# Schematic.net
KiCad netlist of a schematic drawn in Altium Designer
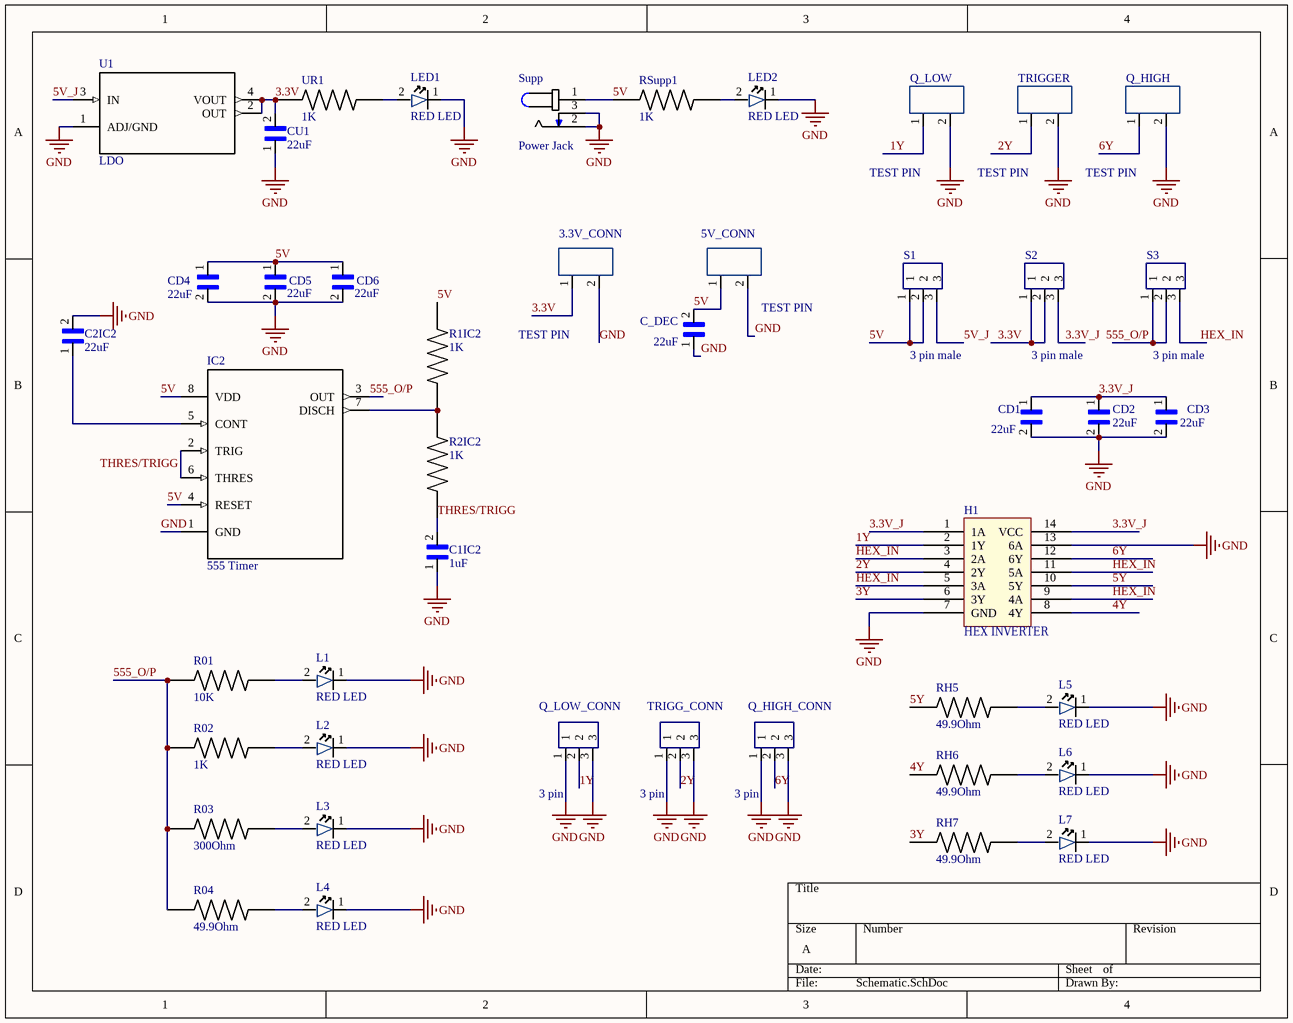
[diagram p0: Schematic.SchDoc]

(export (version "E")
  (design (tool "Eeschema 10.0.6"))
  (components
    (comp (ref "3.3V_CONN")
      (value "TEST PIN")
      (footprint "TEST_PINS")
      (libsource (lib "Components") (part "TEST PIN"))
    )
    (comp (ref "5V_CONN")
      (value "TEST PIN")
      (footprint "TEST_PINS")
      (libsource (lib "Components") (part "TEST PIN"))
    )
    (comp (ref "C1IC2")
      (value "1uF")
      (footprint "1206_PASSIVE")
      (description "CAP CER 1UF 16V X7R 1206")
      (fields (field (name "DIGIKEY PART") "‎399-8150-1-ND‎"))
      (libsource (lib "Components") (part "C1206C105M4RACTU‎"))
    )
    (comp (ref "C2IC2")
      (value "22uF")
      (footprint "1206_PASSIVE")
      (description "CAP CER 22UF 16V X5R 1206")
      (fields (field (name "DIGIKEY PART") "‎1276-2728-1-ND‎"))
      (libsource (lib "Components") (part "CL31A226MOCLNNC‎"))
    )
    (comp (ref "CD1")
      (value "22uF")
      (footprint "1206_PASSIVE")
      (description "CAP CER 22UF 16V X5R 1206")
      (fields (field (name "DIGIKEY PART") "‎1276-2728-1-ND‎"))
      (libsource (lib "Components") (part "CL31A226MOCLNNC‎"))
    )
    (comp (ref "CD2")
      (value "22uF")
      (footprint "1206_PASSIVE")
      (description "CAP CER 22UF 16V X5R 1206")
      (fields (field (name "DIGIKEY PART") "‎1276-2728-1-ND‎"))
      (libsource (lib "Components") (part "CL31A226MOCLNNC‎"))
    )
    (comp (ref "CD3")
      (value "22uF")
      (footprint "1206_PASSIVE")
      (description "CAP CER 22UF 16V X5R 1206")
      (fields (field (name "DIGIKEY PART") "‎1276-2728-1-ND‎"))
      (libsource (lib "Components") (part "CL31A226MOCLNNC‎"))
    )
    (comp (ref "CD4")
      (value "22uF")
      (footprint "1206_PASSIVE")
      (description "CAP CER 22UF 16V X5R 1206")
      (fields (field (name "DIGIKEY PART") "‎1276-2728-1-ND‎"))
      (libsource (lib "Components") (part "CL31A226MOCLNNC‎"))
    )
    (comp (ref "CD5")
      (value "22uF")
      (footprint "1206_PASSIVE")
      (description "CAP CER 22UF 16V X5R 1206")
      (fields (field (name "DIGIKEY PART") "‎1276-2728-1-ND‎"))
      (libsource (lib "Components") (part "CL31A226MOCLNNC‎"))
    )
    (comp (ref "CD6")
      (value "22uF")
      (footprint "1206_PASSIVE")
      (description "CAP CER 22UF 16V X5R 1206")
      (fields (field (name "DIGIKEY PART") "‎1276-2728-1-ND‎"))
      (libsource (lib "Components") (part "CL31A226MOCLNNC‎"))
    )
    (comp (ref "CU1")
      (value "22uF")
      (footprint "1206_PASSIVE")
      (description "CAP CER 22UF 16V X5R 1206")
      (fields (field (name "DIGIKEY PART") "‎1276-2728-1-ND‎"))
      (libsource (lib "Components") (part "CL31A226MOCLNNC‎"))
    )
    (comp (ref "C_DEC")
      (value "22uF")
      (footprint "1206_PASSIVE")
      (description "CAP CER 22UF 16V X5R 1206")
      (fields (field (name "DIGIKEY PART") "‎1276-2728-1-ND‎"))
      (libsource (lib "Components") (part "CL31A226MOCLNNC‎"))
    )
    (comp (ref "H1")
      (value "‎HEX INVERTER")
      (footprint "HEX")
      (description "IC INVERTER SCHMITT 6CH 14SOP")
      (fields (field (name "DIGIKEY PART") "‎296-28498-1-ND‎"))
      (libsource (lib "Components") (part "‎SN74ALVC14NSR‎"))
    )
    (comp (ref "IC2")
      (value "555 Timer")
      (footprint "555")
      (description "IC OSC SGL TIMER 2.1MHZ 8-SOIC")
      (fields (field (name "DIGIKEY PART") "‎296-1336-1-ND‎"))
      (libsource (lib "Components") (part "‎TLC555CDR‎"))
    )
    (comp (ref "L1")
      (value "RED LED")
      (footprint "LED")
      (description "LED RED CLEAR 1206 SMD")
      (fields (field (name "DIGIKEY PART") "160-1167-1-ND‎"))
      (libsource (lib "Components") (part "‎LTST-C150CKT"))
    )
    (comp (ref "L2")
      (value "RED LED")
      (footprint "LED")
      (description "LED RED CLEAR 1206 SMD")
      (fields (field (name "DIGIKEY PART") "160-1167-1-ND‎"))
      (libsource (lib "Components") (part "‎LTST-C150CKT"))
    )
    (comp (ref "L3")
      (value "RED LED")
      (footprint "LED")
      (description "LED RED CLEAR 1206 SMD")
      (fields (field (name "DIGIKEY PART") "160-1167-1-ND‎"))
      (libsource (lib "Components") (part "‎LTST-C150CKT"))
    )
    (comp (ref "L4")
      (value "RED LED")
      (footprint "LED")
      (description "LED RED CLEAR 1206 SMD")
      (fields (field (name "DIGIKEY PART") "160-1167-1-ND‎"))
      (libsource (lib "Components") (part "‎LTST-C150CKT"))
    )
    (comp (ref "L5")
      (value "RED LED")
      (footprint "LED")
      (description "LED RED CLEAR 1206 SMD")
      (fields (field (name "DIGIKEY PART") "160-1167-1-ND‎"))
      (libsource (lib "Components") (part "‎LTST-C150CKT"))
    )
    (comp (ref "L6")
      (value "RED LED")
      (footprint "LED")
      (description "LED RED CLEAR 1206 SMD")
      (fields (field (name "DIGIKEY PART") "160-1167-1-ND‎"))
      (libsource (lib "Components") (part "‎LTST-C150CKT"))
    )
    (comp (ref "L7")
      (value "RED LED")
      (footprint "LED")
      (description "LED RED CLEAR 1206 SMD")
      (fields (field (name "DIGIKEY PART") "160-1167-1-ND‎"))
      (libsource (lib "Components") (part "‎LTST-C150CKT"))
    )
    (comp (ref "LED1")
      (value "RED LED")
      (footprint "LED")
      (description "LED RED CLEAR 1206 SMD")
      (fields (field (name "DIGIKEY PART") "160-1167-1-ND‎"))
      (libsource (lib "Components") (part "‎LTST-C150CKT"))
    )
    (comp (ref "LED2")
      (value "RED LED")
      (footprint "LED")
      (description "LED RED CLEAR 1206 SMD")
      (fields (field (name "DIGIKEY PART") "160-1167-1-ND‎"))
      (libsource (lib "Components") (part "‎LTST-C150CKT"))
    )
    (comp (ref "Q_HIGH")
      (value "TEST PIN")
      (footprint "TEST_PINS")
      (libsource (lib "Components") (part "TEST PIN"))
    )
    (comp (ref "Q_HIGH_CONN")
      (value "3 pin")
      (footprint "3-PIN")
      (description "CONN HEADER VERT 3POS 2.54MM")
      (fields (field (name "DIGIKEY PART") "‎S1012EC-03-ND‎"))
      (libsource (lib "Components") (part "‎PREC003SAAN-RC‎"))
    )
    (comp (ref "Q_LOW")
      (value "TEST PIN")
      (footprint "TEST_PINS")
      (libsource (lib "Components") (part "TEST PIN"))
    )
    (comp (ref "Q_LOW_CONN")
      (value "3 pin")
      (footprint "3-PIN")
      (description "CONN HEADER VERT 3POS 2.54MM")
      (fields (field (name "DIGIKEY PART") "‎S1012EC-03-ND‎"))
      (libsource (lib "Components") (part "‎PREC003SAAN-RC‎"))
    )
    (comp (ref "R01")
      (value "10K")
      (footprint "1206_PASSIVE")
      (description "RES 10K OHM 1% 1/2W 1206")
      (fields (field (name "DIGIKEY PART") "‎RNCP1206FTD10K0CT-ND‎"))
      (libsource (lib "Components") (part "‎RNCP1206FTD10K0‎"))
    )
    (comp (ref "R1IC2")
      (value "1K")
      (footprint "1206_PASSIVE")
      (description "RES 1K OHM 1% 1/2W 1206")
      (fields (field (name "DIGKIEY PART") "RNCP1206FTD1K00CT-ND‎"))
      (libsource (lib "Components") (part "‎RNCP1206FTD1K00CT-ND‎"))
    )
    (comp (ref "R02")
      (value "1K")
      (footprint "1206_PASSIVE")
      (description "RES 1K OHM 1% 1/2W 1206")
      (fields (field (name "DIGKIEY PART") "RNCP1206FTD1K00CT-ND‎"))
      (libsource (lib "Components") (part "‎RNCP1206FTD1K00CT-ND‎"))
    )
    (comp (ref "R2IC2")
      (value "1K")
      (footprint "1206_PASSIVE")
      (description "RES 1K OHM 1% 1/2W 1206")
      (fields (field (name "DIGKIEY PART") "RNCP1206FTD1K00CT-ND‎"))
      (libsource (lib "Components") (part "‎RNCP1206FTD1K00CT-ND‎"))
    )
    (comp (ref "R03")
      (value "300Ohm")
      (footprint "1206_PASSIVE")
      (description "RES 300 OHM 5% 1/4W 1206")
      (fields (field (name "DIGIKEY PART") "RMCF1206JT300RCT-ND‎"))
      (libsource (lib "Components") (part "RMCF1206JT300R‎"))
    )
    (comp (ref "R04")
      (value "49.9Ohm")
      (footprint "1206_PASSIVE")
      (description "RES 49.9 OHM 1% 1/2W 1206")
      (fields (field (name "DIGIKEY PART") "RNCP1206FTD49R9CT-ND‎"))
      (libsource (lib "Components") (part "RNCP1206FTD49R9‎"))
    )
    (comp (ref "RH5")
      (value "49.9Ohm")
      (footprint "1206_PASSIVE")
      (description "RES 49.9 OHM 1% 1/2W 1206")
      (fields (field (name "DIGIKEY PART") "RNCP1206FTD49R9CT-ND‎"))
      (libsource (lib "Components") (part "RNCP1206FTD49R9‎"))
    )
    (comp (ref "RH6")
      (value "49.9Ohm")
      (footprint "1206_PASSIVE")
      (description "RES 49.9 OHM 1% 1/2W 1206")
      (fields (field (name "DIGIKEY PART") "RNCP1206FTD49R9CT-ND‎"))
      (libsource (lib "Components") (part "RNCP1206FTD49R9‎"))
    )
    (comp (ref "RH7")
      (value "49.9Ohm")
      (footprint "1206_PASSIVE")
      (description "RES 49.9 OHM 1% 1/2W 1206")
      (fields (field (name "DIGIKEY PART") "RNCP1206FTD49R9CT-ND‎"))
      (libsource (lib "Components") (part "RNCP1206FTD49R9‎"))
    )
    (comp (ref "RSupp1")
      (value "1K")
      (footprint "1206_PASSIVE")
      (description "RES 1K OHM 1% 1/2W 1206")
      (fields (field (name "DIGKIEY PART") "RNCP1206FTD1K00CT-ND‎"))
      (libsource (lib "Components") (part "‎RNCP1206FTD1K00CT-ND‎"))
    )
    (comp (ref "S1")
      (value "3 pin male")
      (footprint "3-PIN")
      (description "CONN HEADER VERT 3POS 2.54MM")
      (fields (field (name "DIGIKEY PART") "‎S1012EC-03-ND‎"))
      (libsource (lib "Components") (part "‎PREC003SAAN-RC‎"))
    )
    (comp (ref "S2")
      (value "3 pin male")
      (footprint "3-PIN")
      (description "CONN HEADER VERT 3POS 2.54MM")
      (fields (field (name "DIGIKEY PART") "‎S1012EC-03-ND‎"))
      (libsource (lib "Components") (part "‎PREC003SAAN-RC‎"))
    )
    (comp (ref "S3")
      (value "3 pin male")
      (footprint "3-PIN")
      (description "CONN HEADER VERT 3POS 2.54MM")
      (fields (field (name "DIGIKEY PART") "‎S1012EC-03-ND‎"))
      (libsource (lib "Components") (part "‎PREC003SAAN-RC‎"))
    )
    (comp (ref "Supp")
      (value "Power Jack")
      (footprint "Power Jack")
      (description "CONN PWR JACK 2X5.5MM SOLDER")
      (fields (field (name "DIGIKEY PART") "CP-102A-ND‎"))
      (libsource (lib "Components") (part "‎CP-102A-ND‎"))
    )
    (comp (ref "TRIGGER")
      (value "TEST PIN")
      (footprint "TEST_PINS")
      (libsource (lib "Components") (part "TEST PIN"))
    )
    (comp (ref "TRIGG_CONN")
      (value "3 pin")
      (footprint "3-PIN")
      (description "CONN HEADER VERT 3POS 2.54MM")
      (fields (field (name "DIGIKEY PART") "‎S1012EC-03-ND‎"))
      (libsource (lib "Components") (part "‎PREC003SAAN-RC‎"))
    )
    (comp (ref "U1")
      (value "LDO")
      (footprint "LDO")
      (description "IC REG LINEAR 3.3V 800MA SOT223")
      (libsource (lib "Components") (part "AZ1117CH‎"))
    )
    (comp (ref "UR1")
      (value "1K")
      (footprint "1206_PASSIVE")
      (description "RES 1K OHM 1% 1/2W 1206")
      (fields (field (name "DIGKIEY PART") "RNCP1206FTD1K00CT-ND‎"))
      (libsource (lib "Components") (part "‎RNCP1206FTD1K00CT-ND‎"))
    )
  )
  (nets
    (net (code "1") (name "/1Y") (class "Default")
      (node (ref "H1") (pin "2") (pinfunction "1Y_2") (pintype "passive"))
      (node (ref "Q_LOW") (pin "1") (pinfunction "1_1") (pintype "passive"))
      (node (ref "Q_LOW_CONN") (pin "2") (pinfunction "2_2") (pintype "passive"))
    )
    (net (code "2") (name "/2Y") (class "Default")
      (node (ref "H1") (pin "4") (pinfunction "2Y_4") (pintype "passive"))
      (node (ref "TRIGGER") (pin "1") (pinfunction "1_1") (pintype "passive"))
      (node (ref "TRIGG_CONN") (pin "2") (pinfunction "2_2") (pintype "passive"))
    )
    (net (code "3") (name "/3.3V") (class "Default")
      (node (ref "3.3V_CONN") (pin "1") (pinfunction "1_1") (pintype "passive"))
      (node (ref "CU1") (pin "2") (pinfunction "2_2") (pintype "passive"))
      (node (ref "S2") (pin "1") (pinfunction "1_1") (pintype "passive"))
      (node (ref "S2") (pin "2") (pinfunction "2_2") (pintype "passive"))
      (node (ref "U1") (pin "2") (pinfunction "OUT_2") (pintype "output"))
      (node (ref "U1") (pin "4") (pinfunction "VOUT_4") (pintype "output"))
      (node (ref "UR1") (pin "2") (pinfunction "2_2") (pintype "passive"))
    )
    (net (code "4") (name "/3.3V_J") (class "Default")
      (node (ref "CD1") (pin "1") (pinfunction "1_1") (pintype "passive"))
      (node (ref "CD2") (pin "1") (pinfunction "1_1") (pintype "passive"))
      (node (ref "CD3") (pin "1") (pinfunction "1_1") (pintype "passive"))
      (node (ref "H1") (pin "1") (pinfunction "1A_1") (pintype "passive"))
      (node (ref "H1") (pin "14") (pinfunction "VCC_14") (pintype "passive"))
      (node (ref "S2") (pin "3") (pinfunction "3_3") (pintype "passive"))
    )
    (net (code "5") (name "/3Y") (class "Default")
      (node (ref "H1") (pin "6") (pinfunction "3Y_6") (pintype "passive"))
      (node (ref "RH7") (pin "1") (pinfunction "1_1") (pintype "passive"))
    )
    (net (code "6") (name "/4Y") (class "Default")
      (node (ref "H1") (pin "8") (pinfunction "4Y_8") (pintype "passive"))
      (node (ref "RH6") (pin "1") (pinfunction "1_1") (pintype "passive"))
    )
    (net (code "7") (name "/5V") (class "Default")
      (node (ref "5V_CONN") (pin "1") (pinfunction "1_1") (pintype "passive"))
      (node (ref "CD4") (pin "1") (pinfunction "1_1") (pintype "passive"))
      (node (ref "CD5") (pin "1") (pinfunction "1_1") (pintype "passive"))
      (node (ref "CD6") (pin "1") (pinfunction "1_1") (pintype "passive"))
      (node (ref "C_DEC") (pin "2") (pinfunction "2_2") (pintype "passive"))
      (node (ref "IC2") (pin "4") (pinfunction "RESET_4") (pintype "input"))
      (node (ref "IC2") (pin "8") (pinfunction "VDD_8") (pintype "power_in"))
      (node (ref "R1IC2") (pin "2") (pinfunction "2_2") (pintype "passive"))
      (node (ref "RSupp1") (pin "1") (pinfunction "1_1") (pintype "passive"))
      (node (ref "S1") (pin "1") (pinfunction "1_1") (pintype "passive"))
      (node (ref "S1") (pin "2") (pinfunction "2_2") (pintype "passive"))
      (node (ref "Supp") (pin "1") (pinfunction "1_1") (pintype "passive"))
    )
    (net (code "8") (name "/5V_J") (class "Default")
      (node (ref "S1") (pin "3") (pinfunction "3_3") (pintype "passive"))
      (node (ref "U1") (pin "3") (pinfunction "IN_3") (pintype "input"))
    )
    (net (code "9") (name "/5Y") (class "Default")
      (node (ref "H1") (pin "10") (pinfunction "5Y_10") (pintype "passive"))
      (node (ref "RH5") (pin "1") (pinfunction "1_1") (pintype "passive"))
    )
    (net (code "10") (name "/6Y") (class "Default")
      (node (ref "H1") (pin "12") (pinfunction "6Y_12") (pintype "passive"))
      (node (ref "Q_HIGH") (pin "1") (pinfunction "1_1") (pintype "passive"))
      (node (ref "Q_HIGH_CONN") (pin "2") (pinfunction "2_2") (pintype "passive"))
    )
    (net (code "11") (name "/555_O{slash}P") (class "Default")
      (node (ref "IC2") (pin "3") (pinfunction "OUT_3") (pintype "output"))
      (node (ref "R01") (pin "1") (pinfunction "1_1") (pintype "passive"))
      (node (ref "R02") (pin "2") (pinfunction "2_2") (pintype "passive"))
      (node (ref "R03") (pin "1") (pinfunction "1_1") (pintype "passive"))
      (node (ref "R04") (pin "1") (pinfunction "1_1") (pintype "passive"))
    )
    (net (code "12") (name "/HEX_IN") (class "Default")
      (node (ref "H1") (pin "11") (pinfunction "5A_11") (pintype "passive"))
      (node (ref "H1") (pin "3") (pinfunction "2A_3") (pintype "passive"))
      (node (ref "H1") (pin "5") (pinfunction "3A_5") (pintype "passive"))
      (node (ref "H1") (pin "9") (pinfunction "4A_9") (pintype "passive"))
      (node (ref "S3") (pin "3") (pinfunction "3_3") (pintype "passive"))
    )
    (net (code "13") (name "/THRES{slash}TRIGG") (class "Default")
      (node (ref "C1IC2") (pin "2") (pinfunction "2_2") (pintype "passive"))
      (node (ref "R2IC2") (pin "1") (pinfunction "1_1") (pintype "passive"))
    )
    (net (code "14") (name "GND") (class "Default")
      (node (ref "3.3V_CONN") (pin "2") (pinfunction "2_2") (pintype "passive"))
      (node (ref "5V_CONN") (pin "2") (pinfunction "2_2") (pintype "passive"))
      (node (ref "C1IC2") (pin "1") (pinfunction "1_1") (pintype "passive"))
      (node (ref "C2IC2") (pin "2") (pinfunction "2_2") (pintype "passive"))
      (node (ref "CD1") (pin "2") (pinfunction "2_2") (pintype "passive"))
      (node (ref "CD2") (pin "2") (pinfunction "2_2") (pintype "passive"))
      (node (ref "CD3") (pin "2") (pinfunction "2_2") (pintype "passive"))
      (node (ref "CD4") (pin "2") (pinfunction "2_2") (pintype "passive"))
      (node (ref "CD5") (pin "2") (pinfunction "2_2") (pintype "passive"))
      (node (ref "CD6") (pin "2") (pinfunction "2_2") (pintype "passive"))
      (node (ref "CU1") (pin "1") (pinfunction "1_1") (pintype "passive"))
      (node (ref "C_DEC") (pin "1") (pinfunction "1_1") (pintype "passive"))
      (node (ref "H1") (pin "13") (pinfunction "6A_13") (pintype "passive"))
      (node (ref "H1") (pin "7") (pinfunction "GND_7") (pintype "passive"))
      (node (ref "IC2") (pin "1") (pinfunction "GND_1") (pintype "passive"))
      (node (ref "L1") (pin "1") (pinfunction "1_1") (pintype "passive"))
      (node (ref "L2") (pin "1") (pinfunction "1_1") (pintype "passive"))
      (node (ref "L3") (pin "1") (pinfunction "1_1") (pintype "passive"))
      (node (ref "L4") (pin "1") (pinfunction "1_1") (pintype "passive"))
      (node (ref "L5") (pin "1") (pinfunction "1_1") (pintype "passive"))
      (node (ref "L6") (pin "1") (pinfunction "1_1") (pintype "passive"))
      (node (ref "L7") (pin "1") (pinfunction "1_1") (pintype "passive"))
      (node (ref "LED1") (pin "1") (pinfunction "1_1") (pintype "passive"))
      (node (ref "LED2") (pin "1") (pinfunction "1_1") (pintype "passive"))
      (node (ref "Q_HIGH") (pin "2") (pinfunction "2_2") (pintype "passive"))
      (node (ref "Q_HIGH_CONN") (pin "1") (pinfunction "1_1") (pintype "passive"))
      (node (ref "Q_HIGH_CONN") (pin "3") (pinfunction "3_3") (pintype "passive"))
      (node (ref "Q_LOW") (pin "2") (pinfunction "2_2") (pintype "passive"))
      (node (ref "Q_LOW_CONN") (pin "1") (pinfunction "1_1") (pintype "passive"))
      (node (ref "Q_LOW_CONN") (pin "3") (pinfunction "3_3") (pintype "passive"))
      (node (ref "Supp") (pin "2") (pinfunction "2_2") (pintype "passive"))
      (node (ref "Supp") (pin "3") (pinfunction "3_3") (pintype "passive"))
      (node (ref "TRIGGER") (pin "2") (pinfunction "2_2") (pintype "passive"))
      (node (ref "TRIGG_CONN") (pin "1") (pinfunction "1_1") (pintype "passive"))
      (node (ref "TRIGG_CONN") (pin "3") (pinfunction "3_3") (pintype "passive"))
      (node (ref "U1") (pin "1") (pinfunction "ADJ/GND_1") (pintype "passive"))
    )
    (net (code "15") (name "Net-(IC2-CONT)") (class "Default")
      (node (ref "C2IC2") (pin "1") (pinfunction "1_1") (pintype "passive"))
      (node (ref "IC2") (pin "5") (pinfunction "CONT_5") (pintype "input"))
    )
    (net (code "16") (name "Net-(IC2-DISCH)") (class "Default")
      (node (ref "IC2") (pin "7") (pinfunction "DISCH_7") (pintype "output"))
      (node (ref "R1IC2") (pin "1") (pinfunction "1_1") (pintype "passive"))
      (node (ref "R2IC2") (pin "2") (pinfunction "2_2") (pintype "passive"))
    )
    (net (code "17") (name "Net-(IC2-THRES)") (class "Default")
      (node (ref "IC2") (pin "2") (pinfunction "TRIG_2") (pintype "input"))
      (node (ref "IC2") (pin "6") (pinfunction "THRES_6") (pintype "input"))
    )
    (net (code "18") (name "Net-(L1-Pad2)") (class "Default")
      (node (ref "L1") (pin "2") (pinfunction "2_2") (pintype "passive"))
      (node (ref "R01") (pin "2") (pinfunction "2_2") (pintype "passive"))
    )
    (net (code "19") (name "Net-(L2-Pad2)") (class "Default")
      (node (ref "L2") (pin "2") (pinfunction "2_2") (pintype "passive"))
      (node (ref "R02") (pin "1") (pinfunction "1_1") (pintype "passive"))
    )
    (net (code "20") (name "Net-(L3-Pad2)") (class "Default")
      (node (ref "L3") (pin "2") (pinfunction "2_2") (pintype "passive"))
      (node (ref "R03") (pin "2") (pinfunction "2_2") (pintype "passive"))
    )
    (net (code "21") (name "Net-(L4-Pad2)") (class "Default")
      (node (ref "L4") (pin "2") (pinfunction "2_2") (pintype "passive"))
      (node (ref "R04") (pin "2") (pinfunction "2_2") (pintype "passive"))
    )
    (net (code "22") (name "Net-(L5-Pad2)") (class "Default")
      (node (ref "L5") (pin "2") (pinfunction "2_2") (pintype "passive"))
      (node (ref "RH5") (pin "2") (pinfunction "2_2") (pintype "passive"))
    )
    (net (code "23") (name "Net-(L6-Pad2)") (class "Default")
      (node (ref "L6") (pin "2") (pinfunction "2_2") (pintype "passive"))
      (node (ref "RH6") (pin "2") (pinfunction "2_2") (pintype "passive"))
    )
    (net (code "24") (name "Net-(L7-Pad2)") (class "Default")
      (node (ref "L7") (pin "2") (pinfunction "2_2") (pintype "passive"))
      (node (ref "RH7") (pin "2") (pinfunction "2_2") (pintype "passive"))
    )
    (net (code "25") (name "Net-(LED1-Pad2)") (class "Default")
      (node (ref "LED1") (pin "2") (pinfunction "2_2") (pintype "passive"))
      (node (ref "UR1") (pin "1") (pinfunction "1_1") (pintype "passive"))
    )
    (net (code "26") (name "Net-(LED2-Pad2)") (class "Default")
      (node (ref "LED2") (pin "2") (pinfunction "2_2") (pintype "passive"))
      (node (ref "RSupp1") (pin "2") (pinfunction "2_2") (pintype "passive"))
    )
    (net (code "27") (name "Net-(S3-Pad1)") (class "Default")
      (node (ref "S3") (pin "1") (pinfunction "1_1") (pintype "passive"))
      (node (ref "S3") (pin "2") (pinfunction "2_2") (pintype "passive"))
    )
  )
)
